# brick_serial_usb.net
KiCad netlist of a schematic drawn in EAGLE
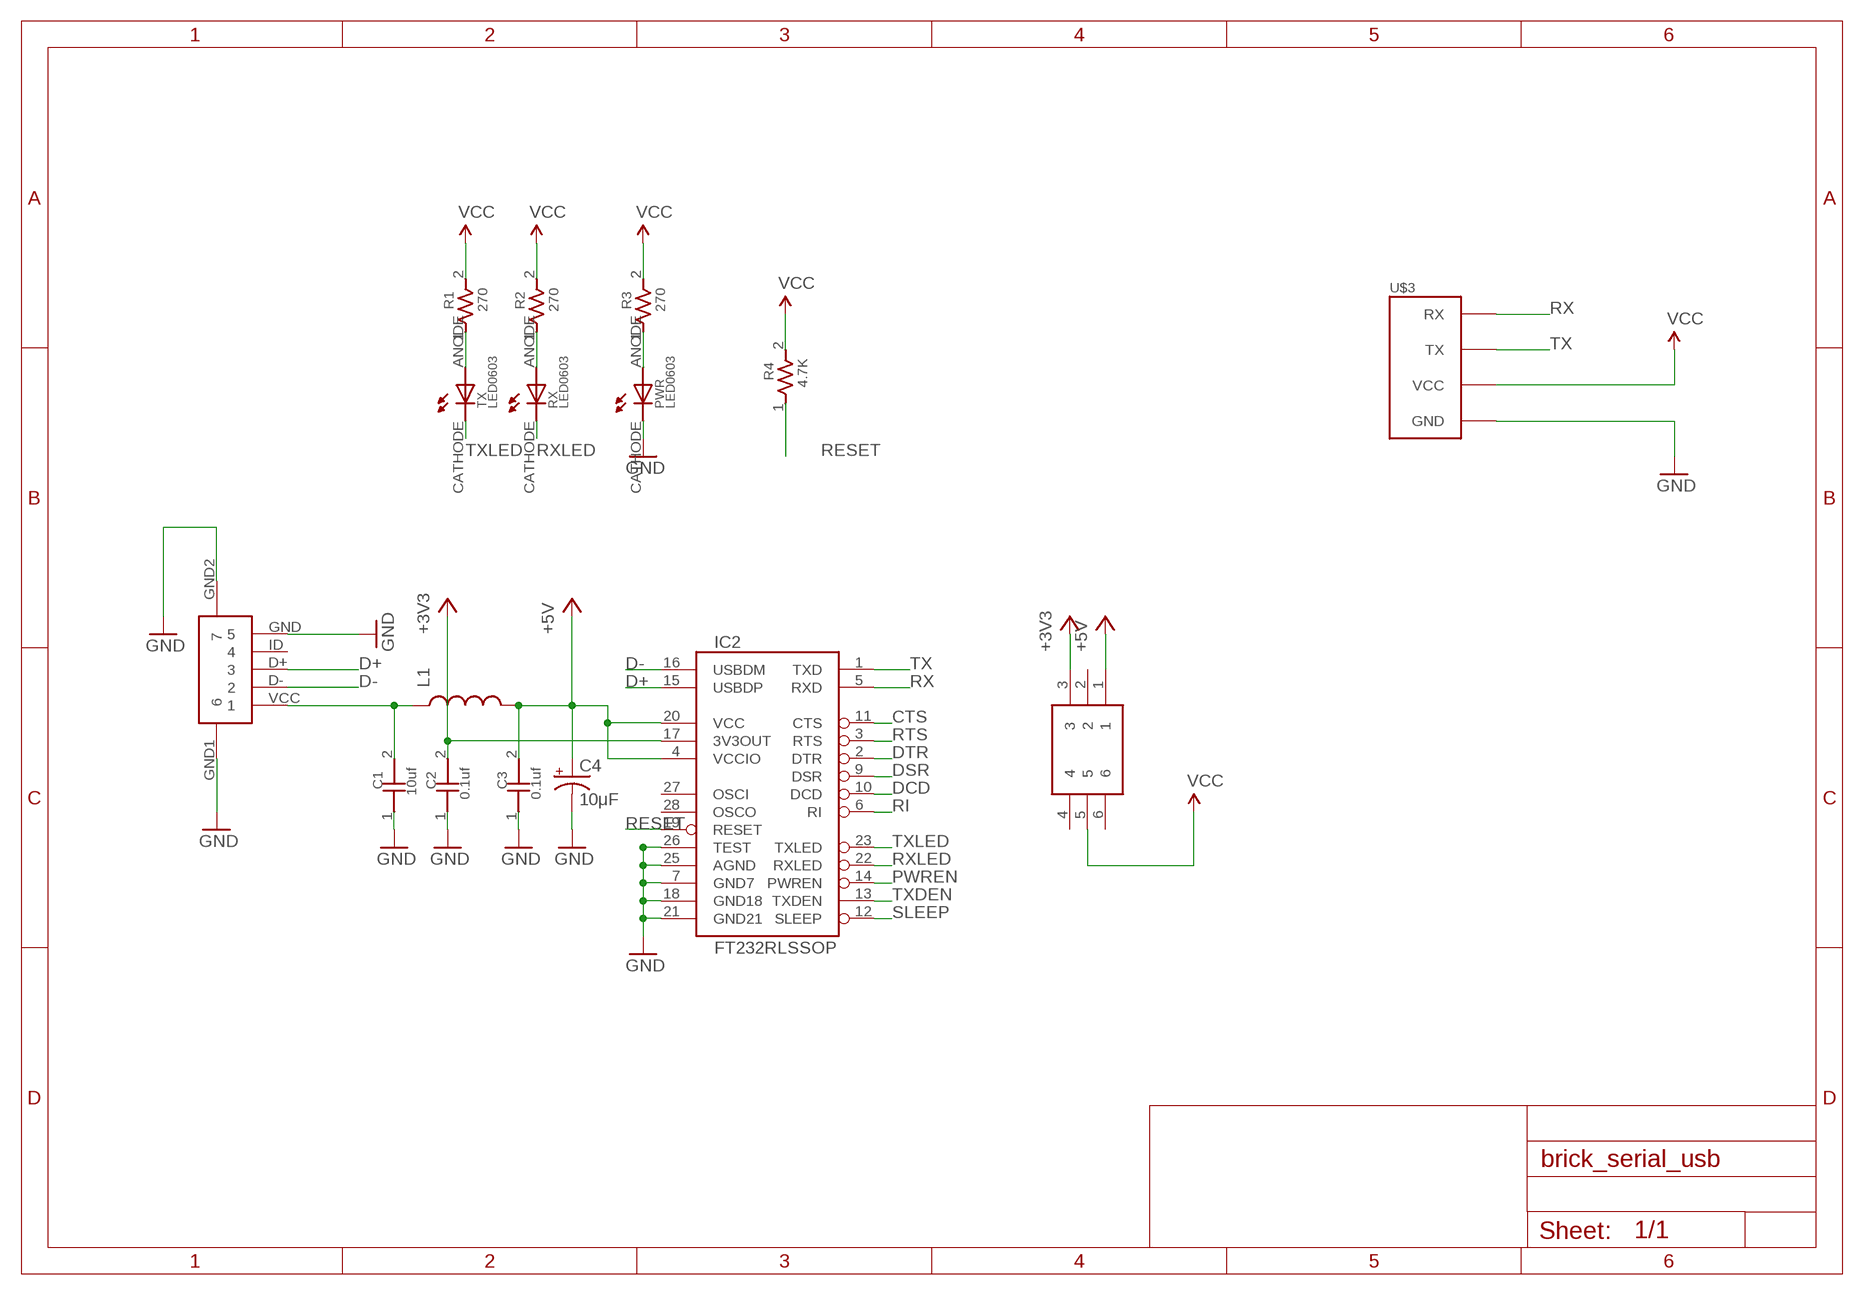
[diagram p0: schematic, sheet 1]

(export (version "E")
  (design (tool "Eeschema 10.0.6"))
  (components
    (comp (ref "C1")
      (value "10uf")
      (footprint "eagle-import:0603")
      (libsource (lib "eagle-import") (part "CAPACITOR0603"))
    )
    (comp (ref "C2")
      (value "0.1uf")
      (footprint "eagle-import:0603")
      (libsource (lib "eagle-import") (part "CAPACITOR0603"))
    )
    (comp (ref "C3")
      (value "0.1uf")
      (footprint "eagle-import:0603")
      (libsource (lib "eagle-import") (part "CAPACITOR0603"))
    )
    (comp (ref "C4")
      (value "10μF")
      (footprint "eagle-import:EIA3216")
      (libsource (lib "eagle-import") (part "CAP_POL1206"))
    )
    (comp (ref "IC2")
      (value "FT232RLSSOP")
      (footprint "eagle-import:SSOP28DB")
      (libsource (lib "eagle-import") (part "FT232RLSSOP"))
    )
    (comp (ref "L1")
      (value "INDUCTOR0603")
      (footprint "eagle-import:0603")
      (libsource (lib "eagle-import") (part "INDUCTOR0603"))
    )
    (comp (ref "PWR")
      (value "LED0603")
      (footprint "eagle-import:0603")
      (libsource (lib "eagle-import") (part "LED0603"))
    )
    (comp (ref "R1")
      (value "270")
      (footprint "eagle-import:0603")
      (libsource (lib "eagle-import") (part "RESISTOR0603"))
    )
    (comp (ref "R2")
      (value "270")
      (footprint "eagle-import:0603")
      (libsource (lib "eagle-import") (part "RESISTOR0603"))
    )
    (comp (ref "R3")
      (value "270")
      (footprint "eagle-import:0603")
      (libsource (lib "eagle-import") (part "RESISTOR0603"))
    )
    (comp (ref "R4")
      (value "4.7K")
      (footprint "eagle-import:0603")
      (libsource (lib "eagle-import") (part "RESISTOR0603"))
    )
    (comp (ref "RX")
      (value "LED0603")
      (footprint "eagle-import:0603")
      (libsource (lib "eagle-import") (part "LED0603"))
    )
    (comp (ref "TX")
      (value "LED0603")
      (footprint "eagle-import:0603")
      (libsource (lib "eagle-import") (part "LED0603"))
    )
    (comp (ref "U$1")
      (value "USB-MICRO-B-FEMALE")
      (footprint "eagle-import:USB-MICRO-B-FEMALE")
      (libsource (lib "eagle-import") (part "USB-MICRO-B-FEMALE"))
    )
    (comp (ref "U$2")
      (value "C&K_JS202011SCQN")
      (footprint "eagle-import:C&K_JS202011SCQN")
      (libsource (lib "eagle-import") (part "C&K_JS202011SCQN"))
    )
    (comp (ref "U$3")
      (value "BRICK_SERIAL")
      (footprint "eagle-import:BRICK_SERIAL")
      (libsource (lib "eagle-import") (part "BRICK_SERIAL"))
    )
  )
  (nets
    (net (code "1") (name "+3V3") (class "Default")
      (node (ref "C2") (pin "2") (pinfunction "2_2") (pintype "passive"))
      (node (ref "IC2") (pin "17") (pinfunction "3V3OUT_17") (pintype "output"))
      (node (ref "U$2") (pin "3") (pinfunction "3_3") (pintype "bidirectional"))
    )
    (net (code "2") (name "+5V") (class "Default")
      (node (ref "C3") (pin "2") (pinfunction "2_2") (pintype "passive"))
      (node (ref "C4") (pin "A") (pinfunction "+_A") (pintype "passive"))
      (node (ref "IC2") (pin "20") (pinfunction "VCC_20") (pintype "power_in"))
      (node (ref "IC2") (pin "4") (pinfunction "VCCIO_4") (pintype "power_in"))
      (node (ref "L1") (pin "2") (pinfunction "2_2") (pintype "passive"))
      (node (ref "U$2") (pin "1") (pinfunction "1_1") (pintype "bidirectional"))
    )
    (net (code "3") (name "/CTS") (class "Default")
      (node (ref "IC2") (pin "11") (pinfunction "CTS_11") (pintype "input"))
    )
    (net (code "4") (name "/D+") (class "Default")
      (node (ref "IC2") (pin "15") (pinfunction "USBDP_15") (pintype "bidirectional"))
      (node (ref "U$1") (pin "D+") (pinfunction "3_D+") (pintype "bidirectional"))
    )
    (net (code "5") (name "/D-") (class "Default")
      (node (ref "IC2") (pin "16") (pinfunction "USBDM_16") (pintype "bidirectional"))
      (node (ref "U$1") (pin "D-") (pinfunction "2_D-") (pintype "bidirectional"))
    )
    (net (code "6") (name "/DCD") (class "Default")
      (node (ref "IC2") (pin "10") (pinfunction "DCD_10") (pintype "input"))
    )
    (net (code "7") (name "/DSR") (class "Default")
      (node (ref "IC2") (pin "9") (pinfunction "DSR_9") (pintype "input"))
    )
    (net (code "8") (name "/DTR") (class "Default")
      (node (ref "IC2") (pin "2") (pinfunction "DTR_2") (pintype "output"))
    )
    (net (code "9") (name "/PWREN") (class "Default")
      (node (ref "IC2") (pin "14") (pinfunction "PWREN_14") (pintype "input"))
    )
    (net (code "10") (name "/RESET") (class "Default")
      (node (ref "IC2") (pin "19") (pinfunction "RESET_19") (pintype "input"))
      (node (ref "R4") (pin "1") (pinfunction "1_1") (pintype "passive"))
    )
    (net (code "11") (name "/RI") (class "Default")
      (node (ref "IC2") (pin "6") (pinfunction "RI_6") (pintype "input"))
    )
    (net (code "12") (name "/RTS") (class "Default")
      (node (ref "IC2") (pin "3") (pinfunction "RTS_3") (pintype "output"))
    )
    (net (code "13") (name "/RX") (class "Default")
      (node (ref "IC2") (pin "5") (pinfunction "RXD_5") (pintype "input"))
      (node (ref "U$3") (pin "RX") (pinfunction "RX_RX") (pintype "bidirectional"))
    )
    (net (code "14") (name "/RXLED") (class "Default")
      (node (ref "IC2") (pin "22") (pinfunction "RXLED_22") (pintype "input"))
      (node (ref "RX") (pin "CATHODE") (pinfunction "CATHODE_CATHODE") (pintype "passive"))
    )
    (net (code "15") (name "/SLEEP") (class "Default")
      (node (ref "IC2") (pin "12") (pinfunction "SLEEP_12") (pintype "input"))
    )
    (net (code "16") (name "/TX") (class "Default")
      (node (ref "IC2") (pin "1") (pinfunction "TXD_1") (pintype "output"))
      (node (ref "U$3") (pin "TX") (pinfunction "TX_TX") (pintype "bidirectional"))
    )
    (net (code "17") (name "/TXDEN") (class "Default")
      (node (ref "IC2") (pin "13") (pinfunction "TXDEN_13") (pintype "input"))
    )
    (net (code "18") (name "/TXLED") (class "Default")
      (node (ref "IC2") (pin "23") (pinfunction "TXLED_23") (pintype "input"))
      (node (ref "TX") (pin "CATHODE") (pinfunction "CATHODE_CATHODE") (pintype "passive"))
    )
    (net (code "19") (name "GND") (class "Default")
      (node (ref "C1") (pin "1") (pinfunction "1_1") (pintype "passive"))
      (node (ref "C2") (pin "1") (pinfunction "1_1") (pintype "passive"))
      (node (ref "C3") (pin "1") (pinfunction "1_1") (pintype "passive"))
      (node (ref "C4") (pin "C") (pinfunction "-_C") (pintype "passive"))
      (node (ref "IC2") (pin "18") (pinfunction "GND18_18") (pintype "power_in"))
      (node (ref "IC2") (pin "21") (pinfunction "GND21_21") (pintype "power_in"))
      (node (ref "IC2") (pin "25") (pinfunction "AGND_25") (pintype "power_in"))
      (node (ref "IC2") (pin "26") (pinfunction "TEST_26") (pintype "input"))
      (node (ref "IC2") (pin "7") (pinfunction "GND7_7") (pintype "power_in"))
      (node (ref "PWR") (pin "CATHODE") (pinfunction "CATHODE_CATHODE") (pintype "passive"))
      (node (ref "U$1") (pin "GND") (pinfunction "5_GND") (pintype "bidirectional"))
      (node (ref "U$1") (pin "GND1") (pinfunction "6_GND1") (pintype "bidirectional"))
      (node (ref "U$1") (pin "GND2") (pinfunction "7_GND2") (pintype "bidirectional"))
      (node (ref "U$3") (pin "GND") (pinfunction "GND_GND") (pintype "bidirectional"))
    )
    (net (code "20") (name "Net-(PWR-PadANODE)") (class "Default")
      (node (ref "PWR") (pin "ANODE") (pinfunction "ANODE_ANODE") (pintype "passive"))
      (node (ref "R3") (pin "1") (pinfunction "1_1") (pintype "passive"))
    )
    (net (code "21") (name "Net-(R1-Pad1)") (class "Default")
      (node (ref "R1") (pin "1") (pinfunction "1_1") (pintype "passive"))
      (node (ref "TX") (pin "ANODE") (pinfunction "ANODE_ANODE") (pintype "passive"))
    )
    (net (code "22") (name "Net-(R2-Pad1)") (class "Default")
      (node (ref "R2") (pin "1") (pinfunction "1_1") (pintype "passive"))
      (node (ref "RX") (pin "ANODE") (pinfunction "ANODE_ANODE") (pintype "passive"))
    )
    (net (code "23") (name "Net-(U$1-1)") (class "Default")
      (node (ref "C1") (pin "2") (pinfunction "2_2") (pintype "passive"))
      (node (ref "L1") (pin "1") (pinfunction "1_1") (pintype "passive"))
      (node (ref "U$1") (pin "VCC") (pinfunction "1_VCC") (pintype "bidirectional"))
    )
    (net (code "24") (name "VCC") (class "Default")
      (node (ref "R1") (pin "2") (pinfunction "2_2") (pintype "passive"))
      (node (ref "R2") (pin "2") (pinfunction "2_2") (pintype "passive"))
      (node (ref "R3") (pin "2") (pinfunction "2_2") (pintype "passive"))
      (node (ref "R4") (pin "2") (pinfunction "2_2") (pintype "passive"))
      (node (ref "U$2") (pin "5") (pinfunction "5_5") (pintype "bidirectional"))
      (node (ref "U$3") (pin "VCC") (pinfunction "VCC_VCC") (pintype "bidirectional"))
    )
    (net (code "25") (name "unconnected-(IC2-OSCI-Pad27)") (class "Default")
      (node (ref "IC2") (pin "27") (pinfunction "OSCI_27") (pintype "input"))
    )
    (net (code "26") (name "unconnected-(IC2-OSCO-Pad28)") (class "Default")
      (node (ref "IC2") (pin "28") (pinfunction "OSCO_28") (pintype "output"))
    )
    (net (code "27") (name "unconnected-(U$1-4-PadID)") (class "Default")
      (node (ref "U$1") (pin "ID") (pinfunction "4_ID") (pintype "bidirectional"))
    )
    (net (code "28") (name "unconnected-(U$2-Pad2)") (class "Default")
      (node (ref "U$2") (pin "2") (pinfunction "2_2") (pintype "bidirectional"))
    )
    (net (code "29") (name "unconnected-(U$2-Pad4)") (class "Default")
      (node (ref "U$2") (pin "4") (pinfunction "4_4") (pintype "bidirectional"))
    )
    (net (code "30") (name "unconnected-(U$2-Pad6)") (class "Default")
      (node (ref "U$2") (pin "6") (pinfunction "6_6") (pintype "bidirectional"))
    )
  )
)
